# arduino_clone.net
KiCad netlist of a schematic drawn in EAGLE
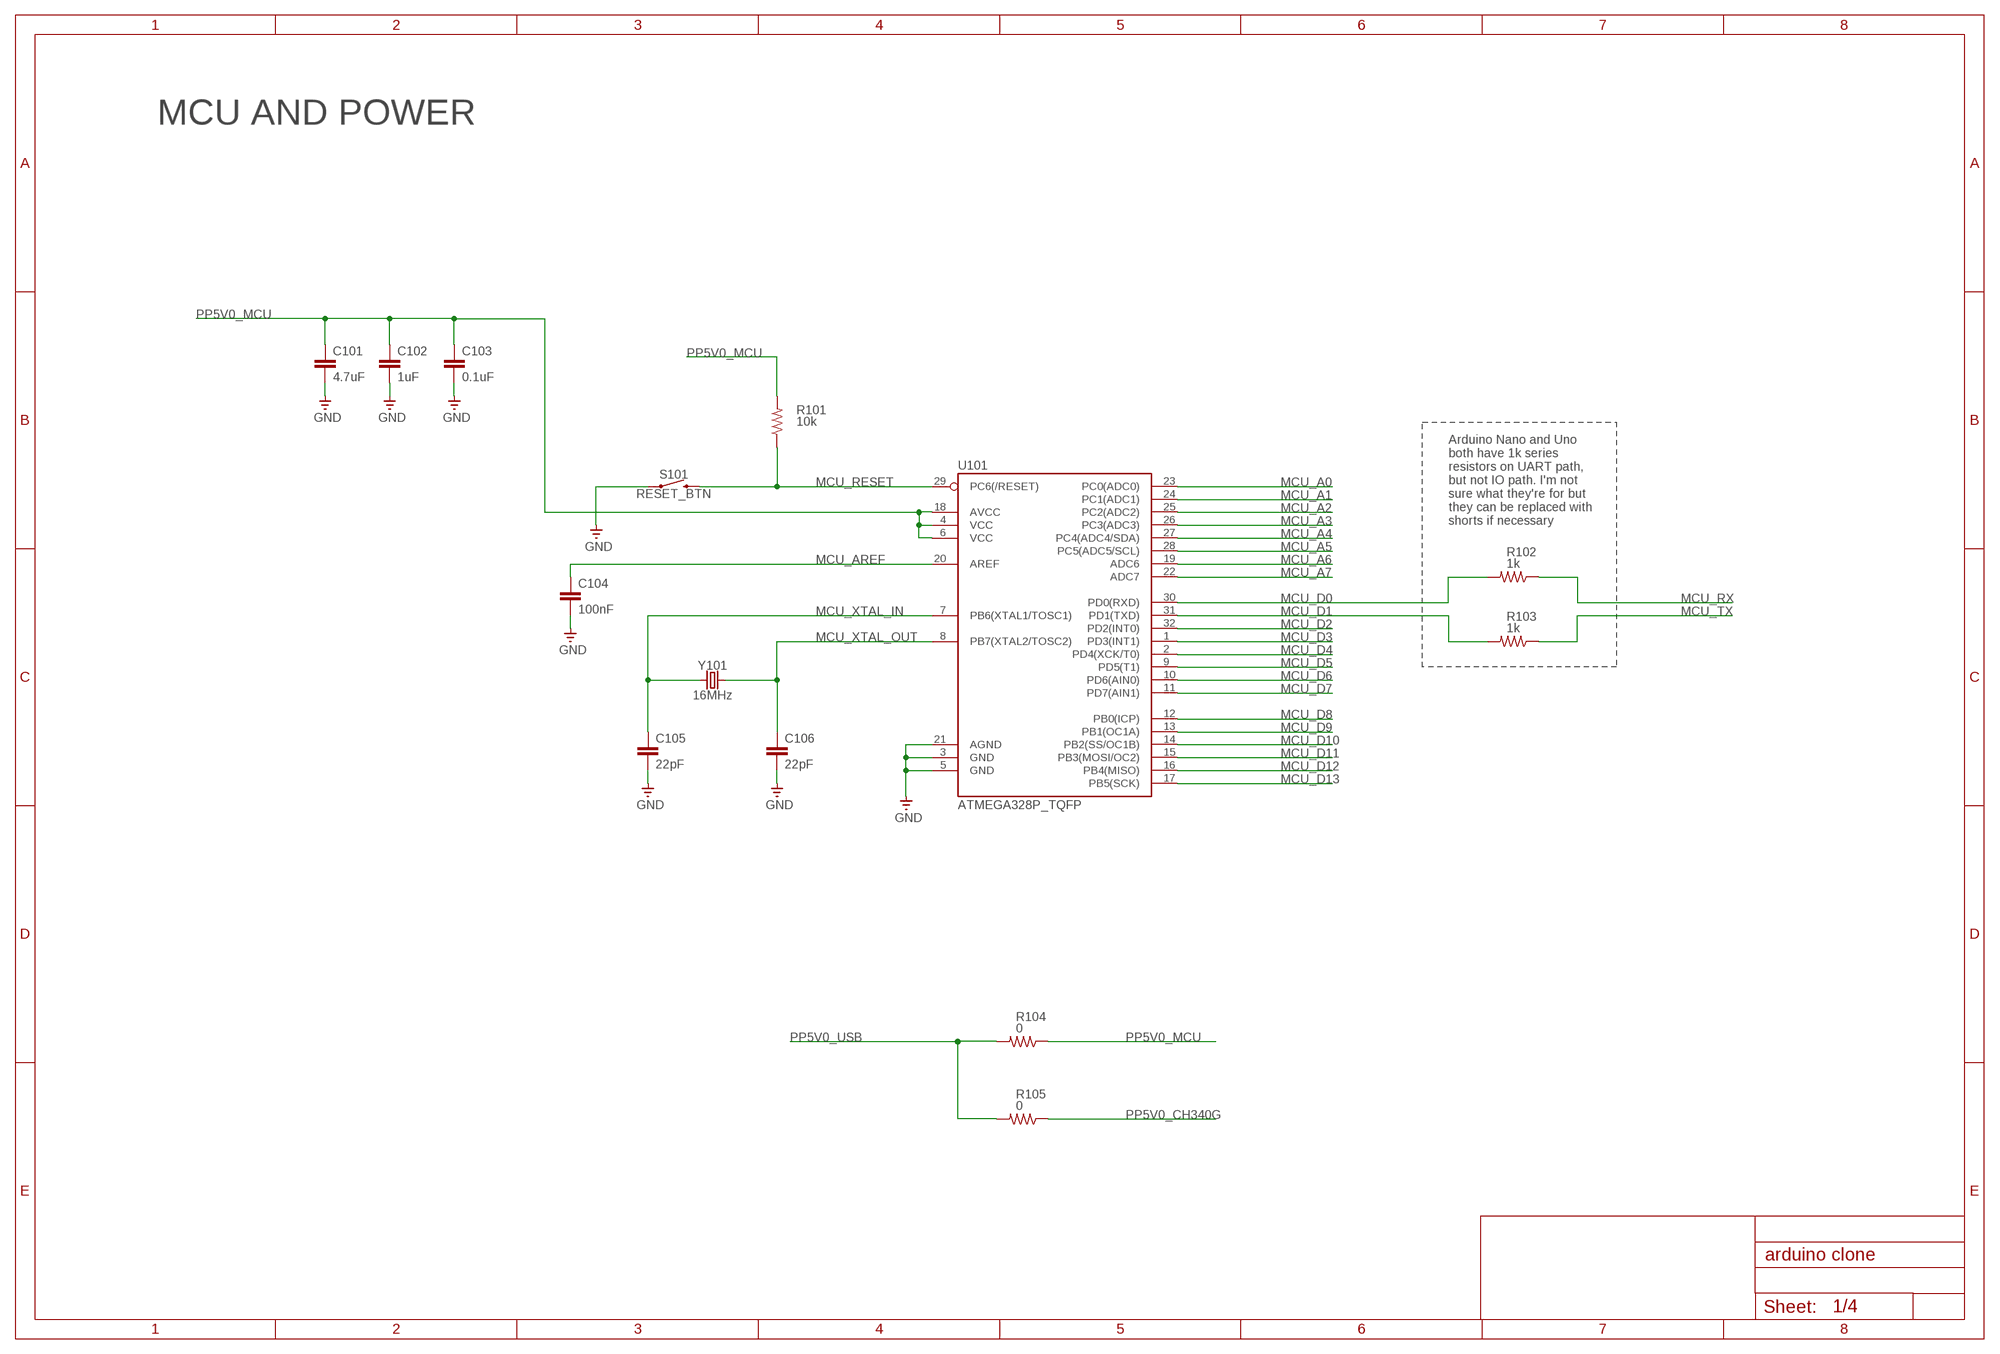
[diagram p0: schematic, sheet 1]
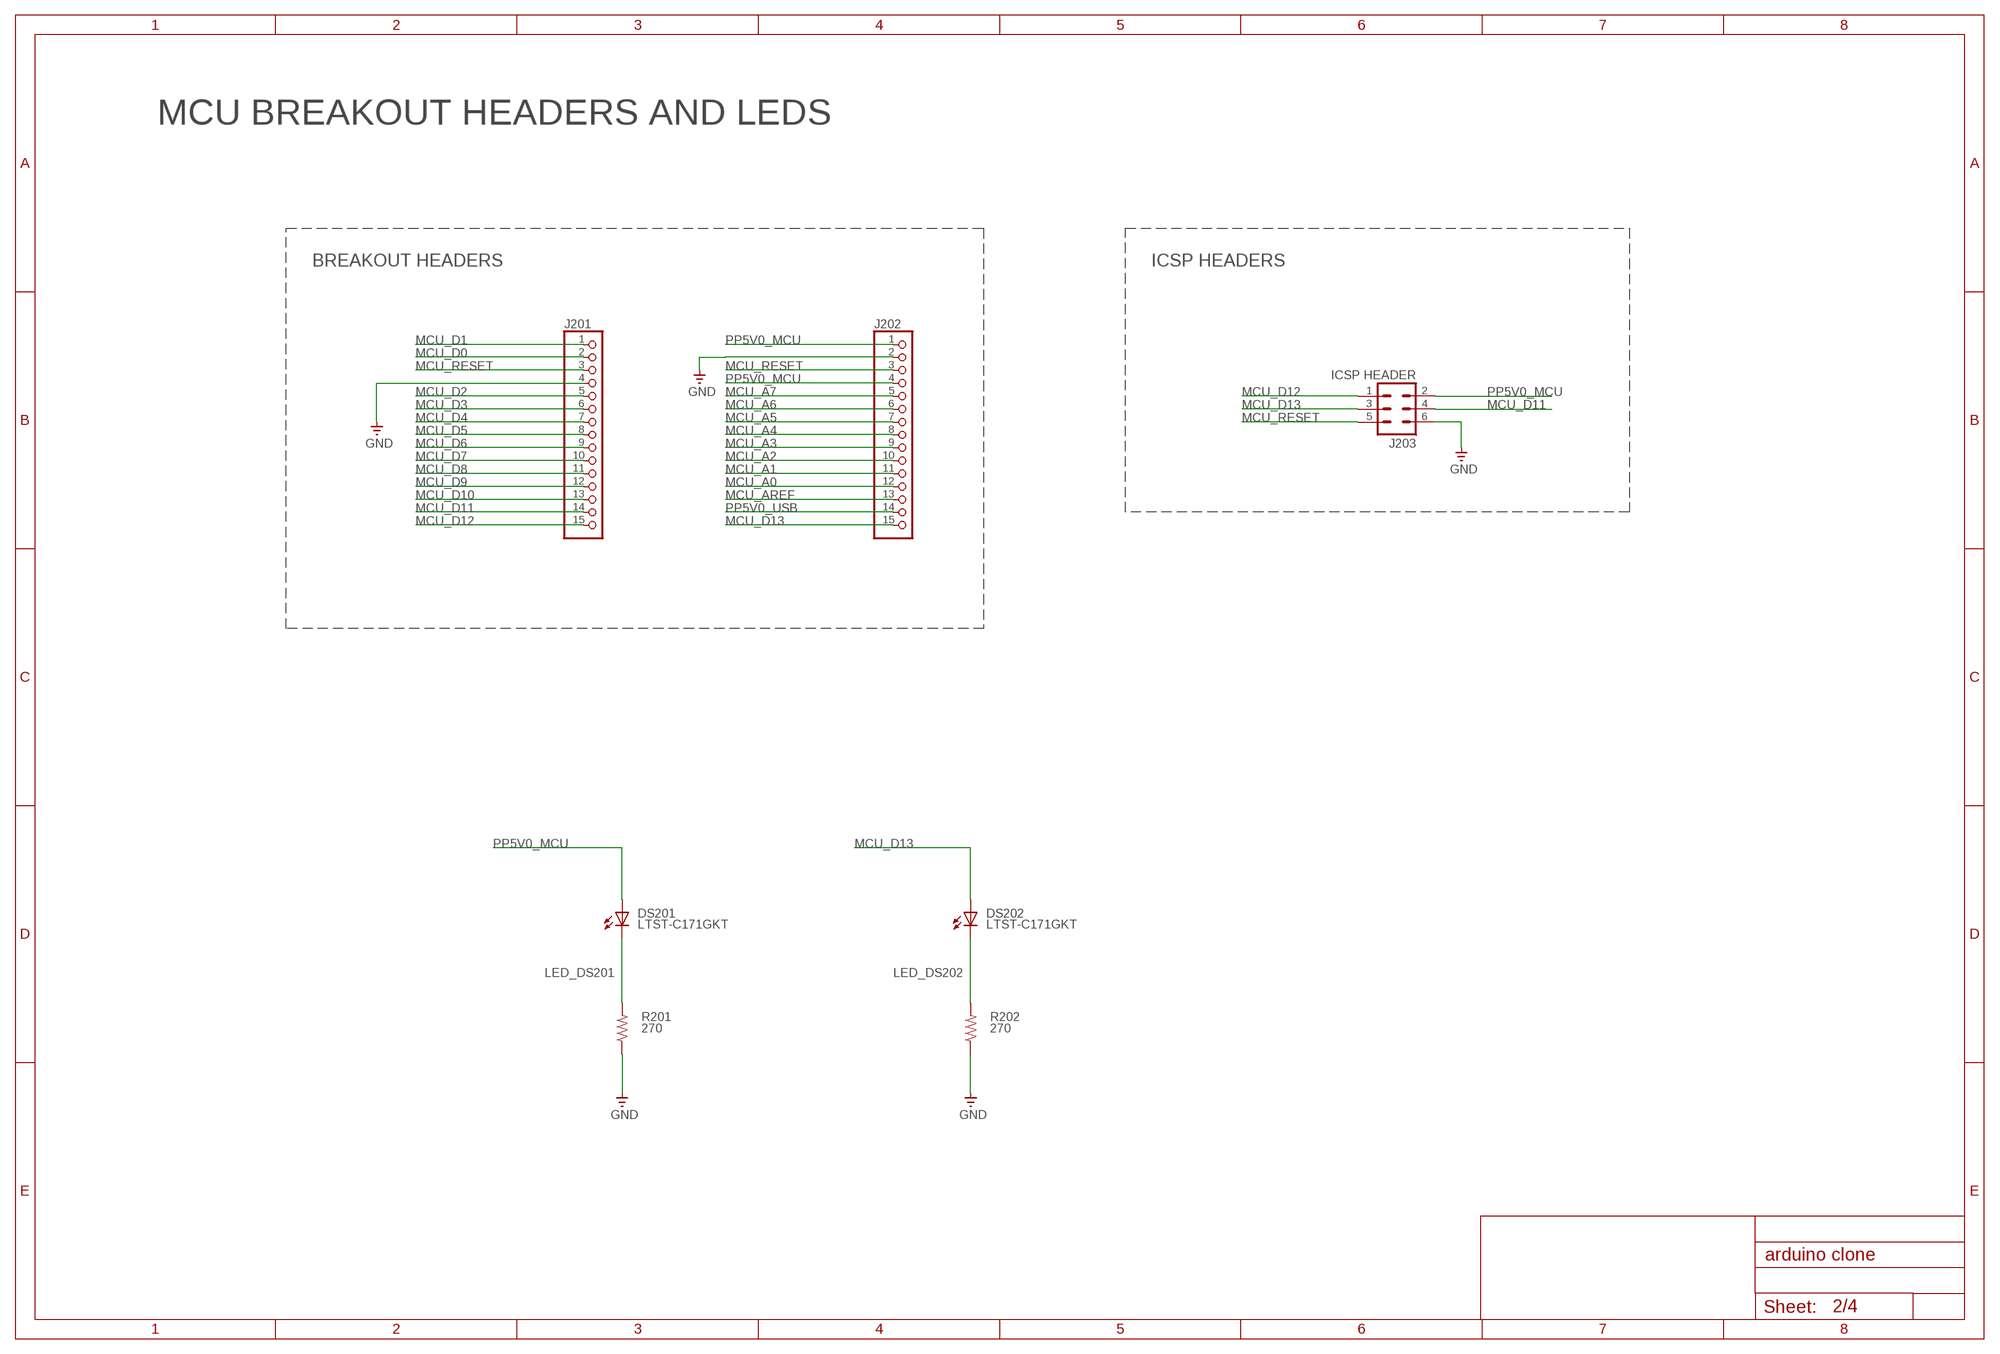
[diagram p1: schematic, sheet 2]
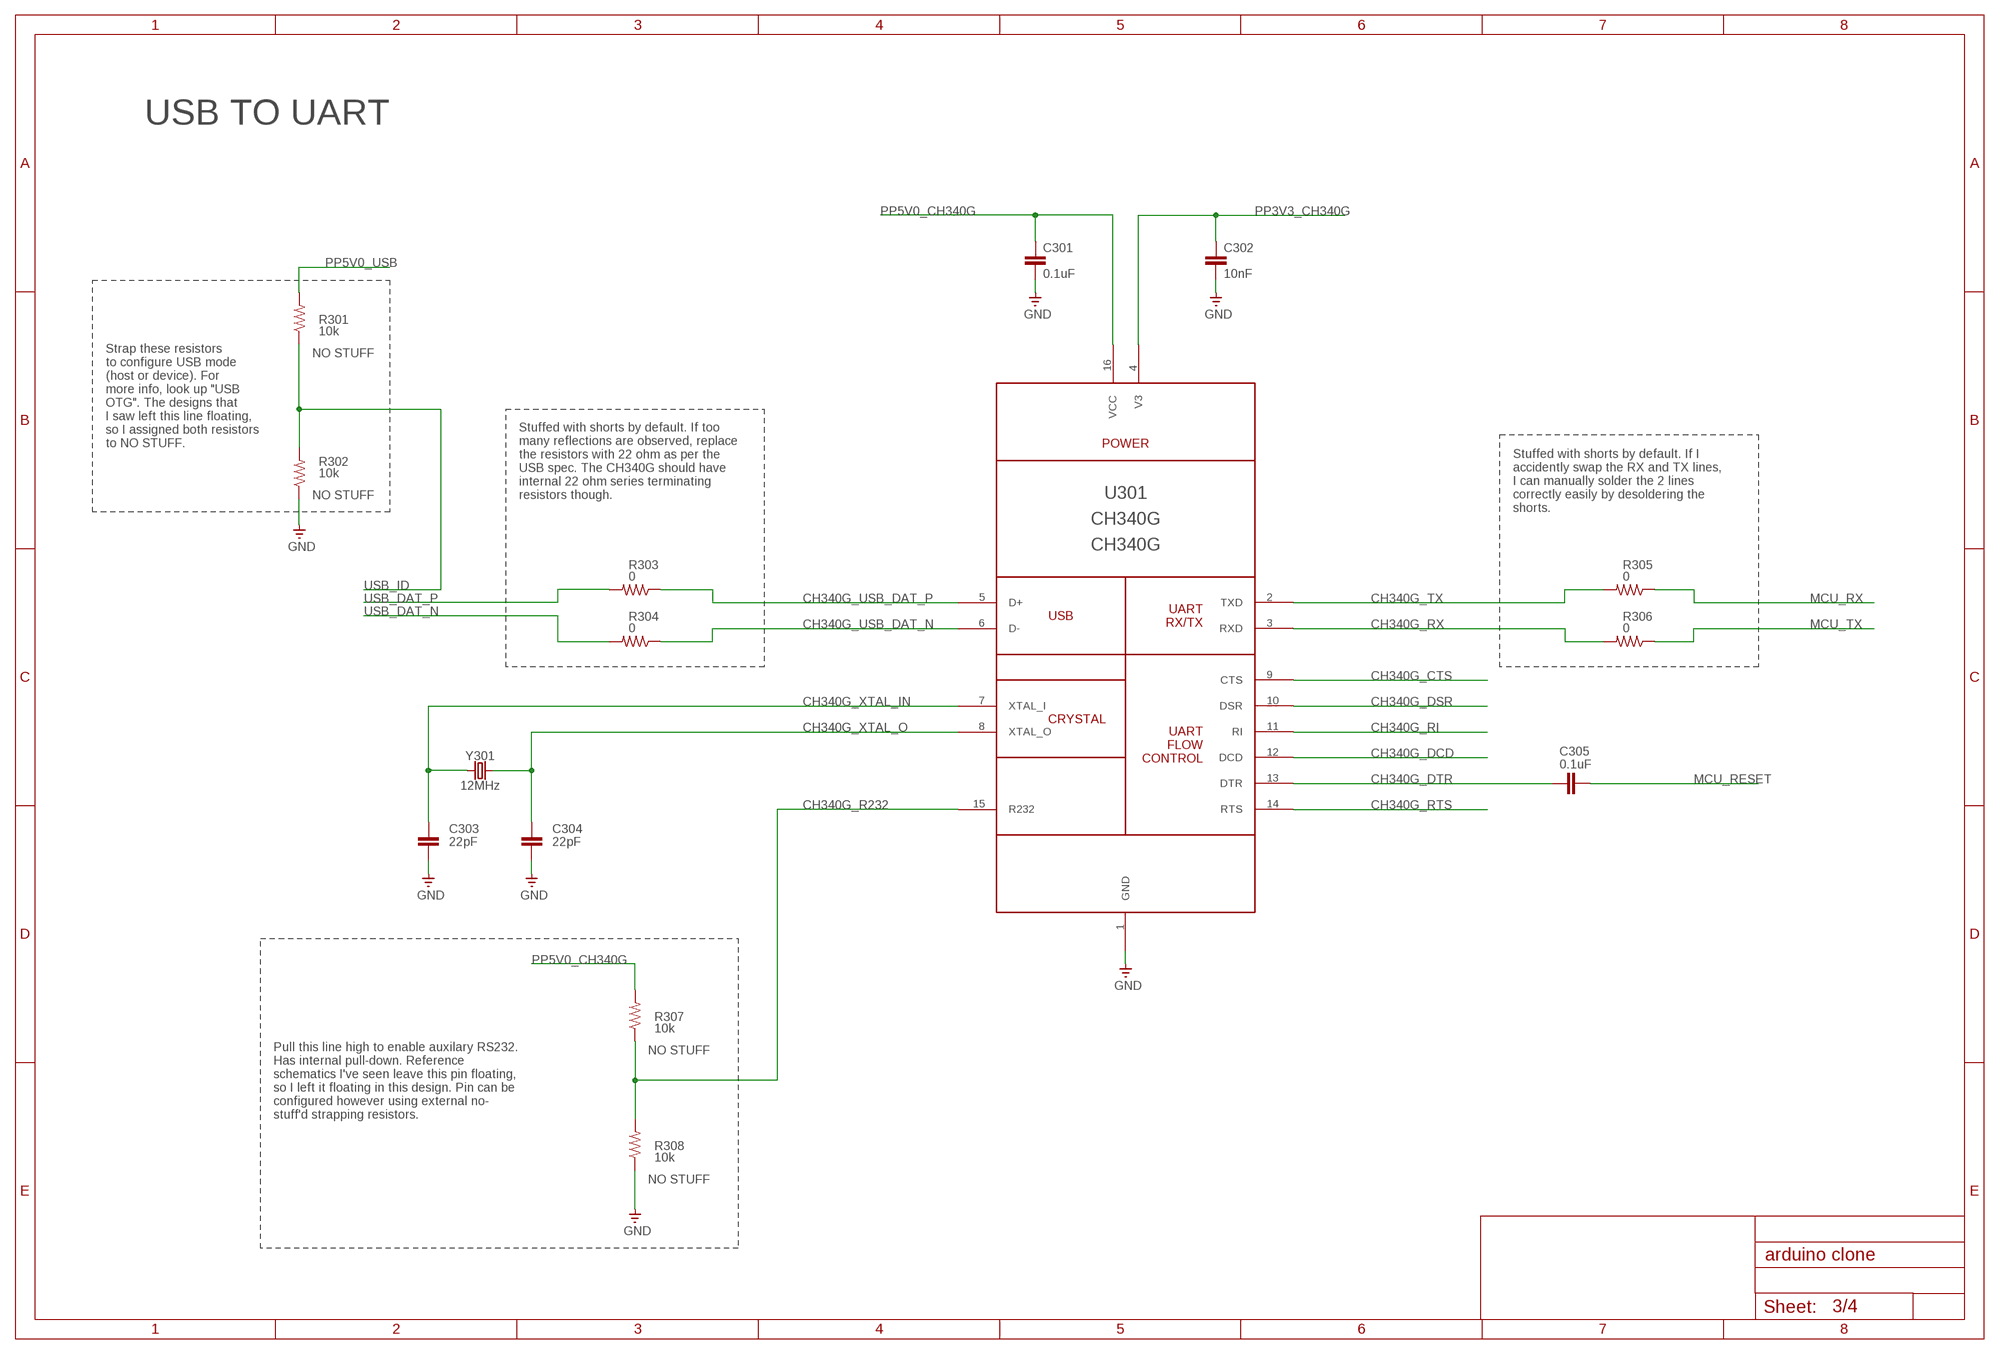
[diagram p2: schematic, sheet 3]
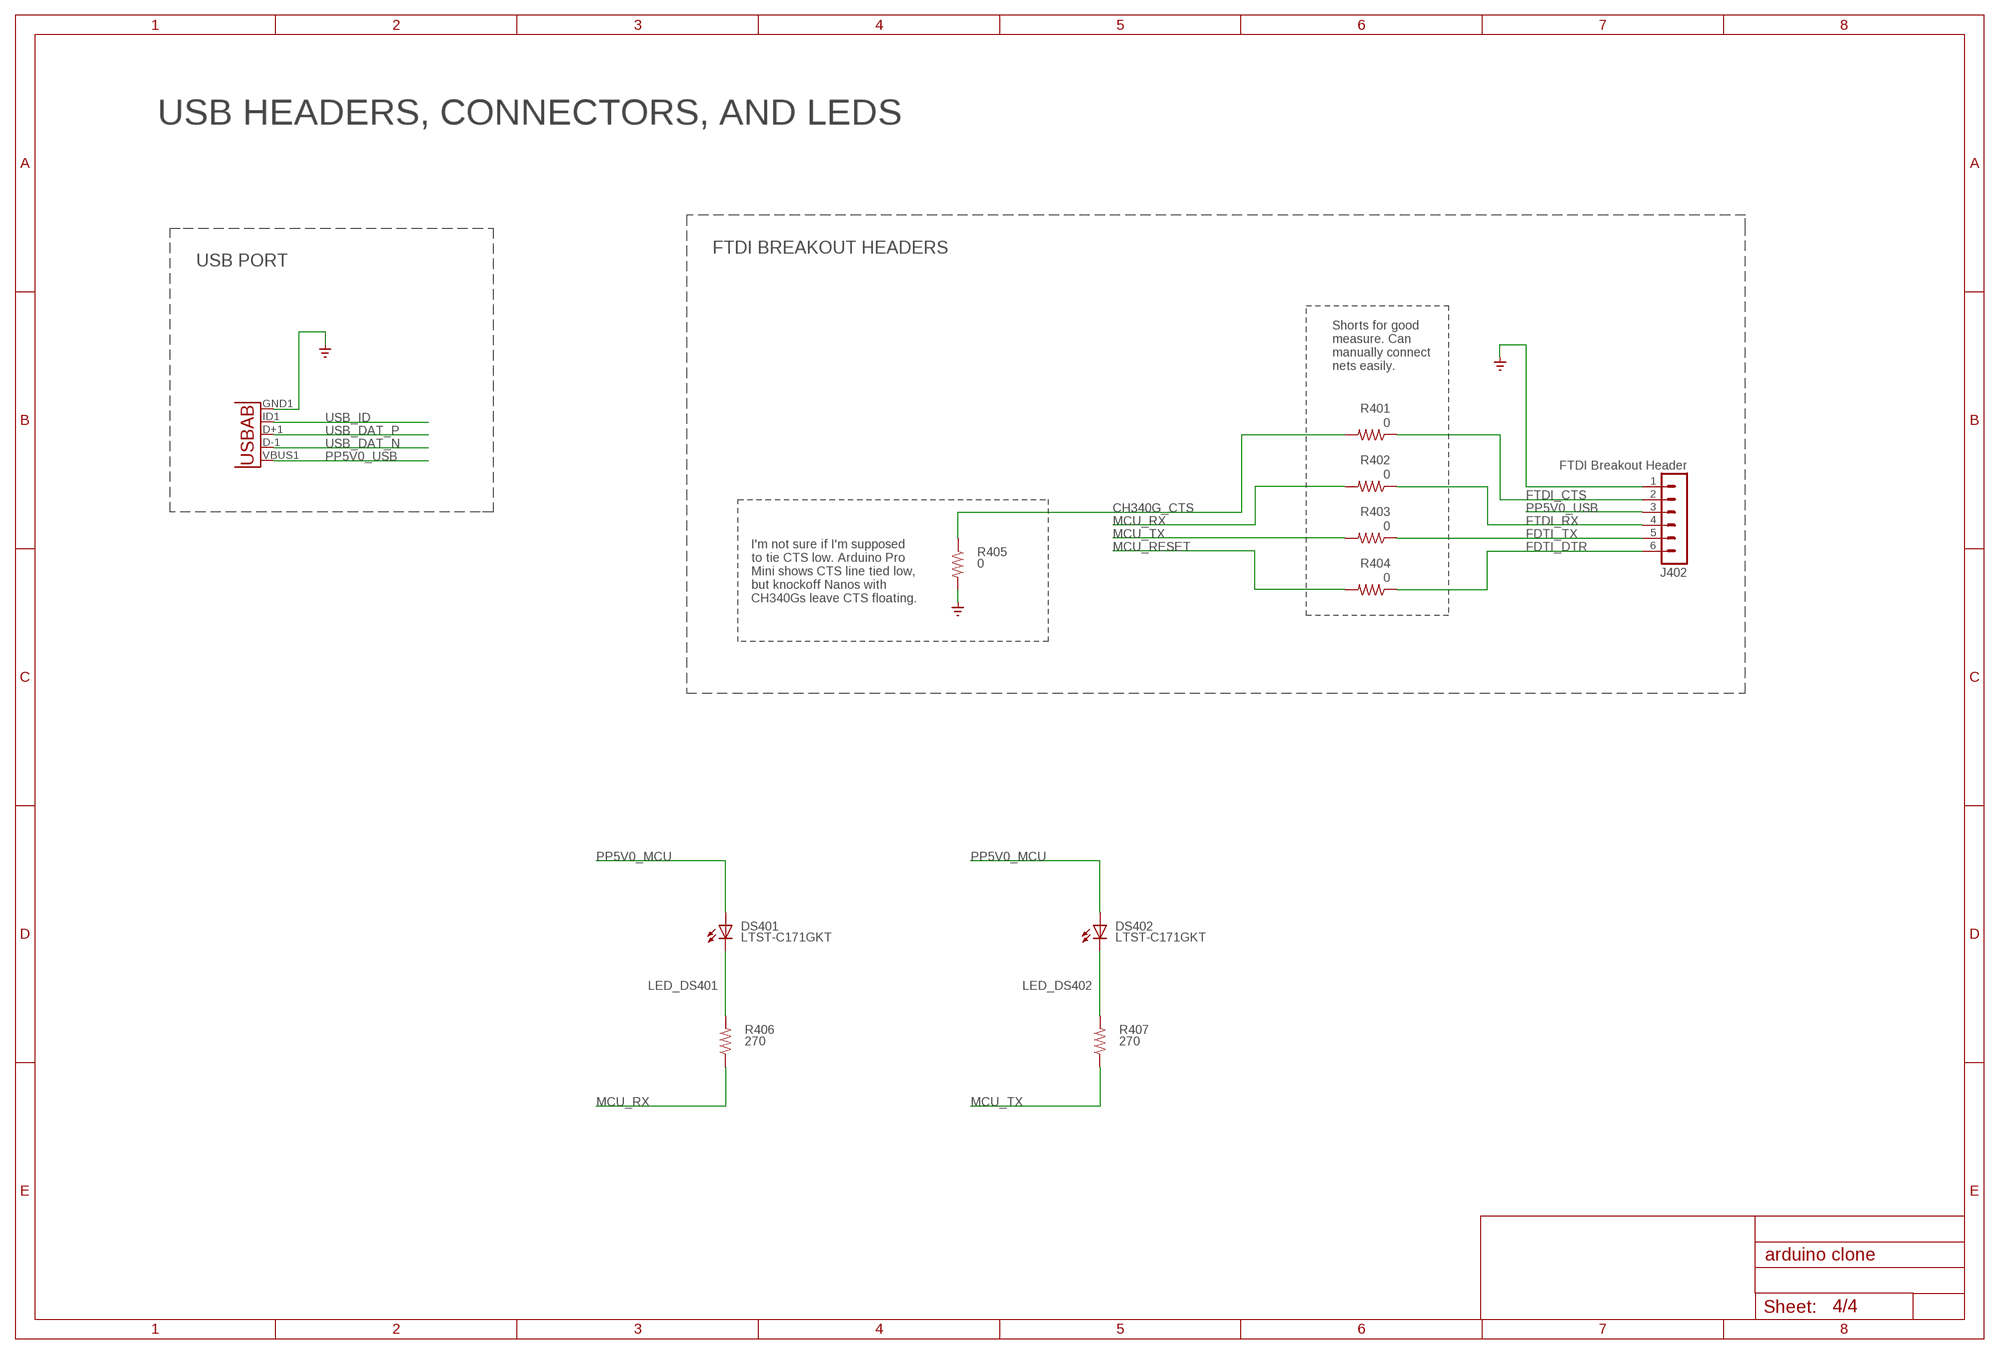
[diagram p3: schematic, sheet 4]

(export (version "E")
  (design (tool "Eeschema 10.0.6"))
  (components
    (comp (ref "C101")
      (value "4.7uF")
      (footprint "eagle-import:C0805")
      (libsource (lib "eagle-import") (part "C-EUC0805"))
    )
    (comp (ref "C102")
      (value "1uF")
      (footprint "eagle-import:C0805")
      (libsource (lib "eagle-import") (part "C-EUC0805"))
    )
    (comp (ref "C103")
      (value "0.1uF")
      (footprint "eagle-import:C0805")
      (libsource (lib "eagle-import") (part "C-EUC0805"))
    )
    (comp (ref "C104")
      (value "100nF")
      (footprint "eagle-import:C0805")
      (libsource (lib "eagle-import") (part "C-EUC0805"))
    )
    (comp (ref "C105")
      (value "22pF")
      (footprint "eagle-import:C0805")
      (libsource (lib "eagle-import") (part "C-EUC0805"))
    )
    (comp (ref "C106")
      (value "22pF")
      (footprint "eagle-import:C0805")
      (libsource (lib "eagle-import") (part "C-EUC0805"))
    )
    (comp (ref "R101")
      (value "10k")
      (footprint "eagle-import:R0805")
      (libsource (lib "eagle-import") (part "R-US_R0805"))
    )
    (comp (ref "R102")
      (value "1k")
      (footprint "eagle-import:R0805")
      (libsource (lib "eagle-import") (part "R-US_R0805"))
    )
    (comp (ref "R103")
      (value "1k")
      (footprint "eagle-import:R0805")
      (libsource (lib "eagle-import") (part "R-US_R0805"))
    )
    (comp (ref "R104")
      (value "0")
      (footprint "eagle-import:R0805")
      (libsource (lib "eagle-import") (part "R-US_R0805"))
    )
    (comp (ref "R105")
      (value "0")
      (footprint "eagle-import:R0805")
      (libsource (lib "eagle-import") (part "R-US_R0805"))
    )
    (comp (ref "S101")
      (value "RESET_BTN")
      (footprint "eagle-import:TACTILE_SWITCH_SMD_6.2MM_TALL")
      (libsource (lib "eagle-import") (part "MOMENTARY-SWITCH-SPST-SMD-6.2MM-TALL"))
    )
    (comp (ref "U101")
      (value "ATMEGA328P_TQFP")
      (footprint "eagle-import:TQFP32-08")
      (libsource (lib "eagle-import") (part "ATMEGA328P_TQFP"))
    )
    (comp (ref "Y101")
      (value "16MHz")
      (footprint "eagle-import:CRYSTAL-SMD-5X3.2-4PAD")
      (libsource (lib "eagle-import") (part "CRYSTAL-16MHZSMD-5X3.2"))
    )
    (comp (ref "C301")
      (value "0.1uF")
      (footprint "eagle-import:C0805")
      (libsource (lib "eagle-import") (part "C-EUC0805"))
    )
    (comp (ref "C302")
      (value "10nF")
      (footprint "eagle-import:C0805")
      (libsource (lib "eagle-import") (part "C-EUC0805"))
    )
    (comp (ref "C303")
      (value "22pF")
      (footprint "eagle-import:C0805")
      (libsource (lib "eagle-import") (part "C-EUC0805"))
    )
    (comp (ref "C304")
      (value "22pF")
      (footprint "eagle-import:C0805")
      (libsource (lib "eagle-import") (part "C-EUC0805"))
    )
    (comp (ref "C305")
      (value "0.1uF")
      (footprint "eagle-import:C0805")
      (libsource (lib "eagle-import") (part "C-EUC0805"))
    )
    (comp (ref "R301")
      (value "10k")
      (footprint "eagle-import:R0805")
      (fields (field (name "STUFF") "NO STUFF"))
      (libsource (lib "eagle-import") (part "R-US_R0805"))
    )
    (comp (ref "R302")
      (value "10k")
      (footprint "eagle-import:R0805")
      (fields (field (name "STUFF") "NO STUFF"))
      (libsource (lib "eagle-import") (part "R-US_R0805"))
    )
    (comp (ref "R303")
      (value "0")
      (footprint "eagle-import:R0805")
      (libsource (lib "eagle-import") (part "R-US_R0805"))
    )
    (comp (ref "R304")
      (value "0")
      (footprint "eagle-import:R0805")
      (libsource (lib "eagle-import") (part "R-US_R0805"))
    )
    (comp (ref "R305")
      (value "0")
      (footprint "eagle-import:R0805")
      (libsource (lib "eagle-import") (part "R-US_R0805"))
    )
    (comp (ref "R306")
      (value "0")
      (footprint "eagle-import:R0805")
      (libsource (lib "eagle-import") (part "R-US_R0805"))
    )
    (comp (ref "R307")
      (value "10k")
      (footprint "eagle-import:R0805")
      (fields (field (name "STUFF") "NO STUFF"))
      (libsource (lib "eagle-import") (part "R-US_R0805"))
    )
    (comp (ref "R308")
      (value "10k")
      (footprint "eagle-import:R0805")
      (fields (field (name "STUFF") "NO STUFF"))
      (libsource (lib "eagle-import") (part "R-US_R0805"))
    )
    (comp (ref "U301")
      (value "CH340G")
      (footprint "eagle-import:SOIC16")
      (libsource (lib "eagle-import") (part "CH340G"))
    )
    (comp (ref "Y301")
      (value "12MHz")
      (footprint "eagle-import:CRYSTAL-SMD-5X3.2-4PAD")
      (libsource (lib "eagle-import") (part "CRYSTAL-12MHZ{dblquote}"))
    )
    (comp (ref "DS201")
      (value "LTST-C171GKT")
      (footprint "eagle-import:CHIPLED_0805")
      (libsource (lib "eagle-import") (part "LEDCHIPLED_0805"))
    )
    (comp (ref "DS202")
      (value "LTST-C171GKT")
      (footprint "eagle-import:CHIPLED_0805")
      (libsource (lib "eagle-import") (part "LEDCHIPLED_0805"))
    )
    (comp (ref "J201")
      (value "PINHD-1X15-CB")
      (footprint "eagle-import:1X15-CB")
      (libsource (lib "eagle-import") (part "PINHD-1X15-CB"))
    )
    (comp (ref "J202")
      (value "PINHD-1X15-CB")
      (footprint "eagle-import:1X15-CB")
      (libsource (lib "eagle-import") (part "PINHD-1X15-CB"))
    )
    (comp (ref "J203")
      (value "ICSP HEADER")
      (footprint "eagle-import:MA03-2")
      (libsource (lib "eagle-import") (part "MA03-2"))
    )
    (comp (ref "R201")
      (value "270")
      (footprint "eagle-import:M0805")
      (libsource (lib "eagle-import") (part "R-US_M0805"))
    )
    (comp (ref "R202")
      (value "270")
      (footprint "eagle-import:M0805")
      (libsource (lib "eagle-import") (part "R-US_M0805"))
    )
    (comp (ref "DS401")
      (value "LTST-C171GKT")
      (footprint "eagle-import:CHIPLED_0805")
      (libsource (lib "eagle-import") (part "LEDCHIPLED_0805"))
    )
    (comp (ref "DS402")
      (value "LTST-C171GKT")
      (footprint "eagle-import:CHIPLED_0805")
      (libsource (lib "eagle-import") (part "LEDCHIPLED_0805"))
    )
    (comp (ref "J401")
      (value "USB-ABIN&OUT")
      (footprint "eagle-import:USB-AB-MICRO-SMD-V03-IN&OUT")
      (libsource (lib "eagle-import") (part "USB-ABIN&OUT"))
    )
    (comp (ref "J402")
      (value "FTDI Breakout Header")
      (footprint "eagle-import:MA06-1")
      (libsource (lib "eagle-import") (part "MA06-1"))
    )
    (comp (ref "R401")
      (value "0")
      (footprint "eagle-import:R0805")
      (libsource (lib "eagle-import") (part "R-US_R0805"))
    )
    (comp (ref "R402")
      (value "0")
      (footprint "eagle-import:R0805")
      (libsource (lib "eagle-import") (part "R-US_R0805"))
    )
    (comp (ref "R403")
      (value "0")
      (footprint "eagle-import:R0805")
      (libsource (lib "eagle-import") (part "R-US_R0805"))
    )
    (comp (ref "R404")
      (value "0")
      (footprint "eagle-import:R0805")
      (libsource (lib "eagle-import") (part "R-US_R0805"))
    )
    (comp (ref "R405")
      (value "0")
      (footprint "eagle-import:R0805")
      (libsource (lib "eagle-import") (part "R-US_R0805"))
    )
    (comp (ref "R406")
      (value "270")
      (footprint "eagle-import:M0805")
      (libsource (lib "eagle-import") (part "R-US_M0805"))
    )
    (comp (ref "R407")
      (value "270")
      (footprint "eagle-import:M0805")
      (libsource (lib "eagle-import") (part "R-US_M0805"))
    )
  )
  (nets
    (net (code "1") (name "CH340G_CTS") (class "Default")
      (node (ref "R401") (pin "2") (pinfunction "2_2") (pintype "passive"))
      (node (ref "R405") (pin "1") (pinfunction "1_1") (pintype "passive"))
      (node (ref "U301") (pin "9") (pinfunction "CTS_9") (pintype "input"))
    )
    (net (code "2") (name "CH340G_DCD") (class "Default")
      (node (ref "U301") (pin "12") (pinfunction "DCD_12") (pintype "input"))
    )
    (net (code "3") (name "CH340G_DSR") (class "Default")
      (node (ref "U301") (pin "10") (pinfunction "DSR_10") (pintype "input"))
    )
    (net (code "4") (name "CH340G_DTR") (class "Default")
      (node (ref "C305") (pin "1") (pinfunction "1_1") (pintype "passive"))
      (node (ref "U301") (pin "13") (pinfunction "DTR_13") (pintype "output"))
    )
    (net (code "5") (name "CH340G_R232") (class "Default")
      (node (ref "R307") (pin "1") (pinfunction "1_1") (pintype "passive"))
      (node (ref "R308") (pin "2") (pinfunction "2_2") (pintype "passive"))
      (node (ref "U301") (pin "15") (pinfunction "R232_15") (pintype "input"))
    )
    (net (code "6") (name "CH340G_RI") (class "Default")
      (node (ref "U301") (pin "11") (pinfunction "RI_11") (pintype "input"))
    )
    (net (code "7") (name "CH340G_RTS") (class "Default")
      (node (ref "U301") (pin "14") (pinfunction "RTS_14") (pintype "output"))
    )
    (net (code "8") (name "CH340G_RX") (class "Default")
      (node (ref "R306") (pin "2") (pinfunction "2_2") (pintype "passive"))
      (node (ref "U301") (pin "3") (pinfunction "RXD_3") (pintype "output"))
    )
    (net (code "9") (name "CH340G_TX") (class "Default")
      (node (ref "R305") (pin "2") (pinfunction "2_2") (pintype "passive"))
      (node (ref "U301") (pin "2") (pinfunction "TXD_2") (pintype "output"))
    )
    (net (code "10") (name "CH340G_USB_DAT_N") (class "Default")
      (node (ref "R304") (pin "1") (pinfunction "1_1") (pintype "passive"))
      (node (ref "U301") (pin "6") (pinfunction "D-_6") (pintype "bidirectional"))
    )
    (net (code "11") (name "CH340G_USB_DAT_P") (class "Default")
      (node (ref "R303") (pin "1") (pinfunction "1_1") (pintype "passive"))
      (node (ref "U301") (pin "5") (pinfunction "D+_5") (pintype "bidirectional"))
    )
    (net (code "12") (name "CH340G_XTAL_IN") (class "Default")
      (node (ref "C303") (pin "1") (pinfunction "1_1") (pintype "passive"))
      (node (ref "U301") (pin "7") (pinfunction "XTAL_I_7") (pintype "bidirectional"))
      (node (ref "Y301") (pin "1") (pinfunction "1_1") (pintype "passive"))
    )
    (net (code "13") (name "CH340G_XTAL_O") (class "Default")
      (node (ref "C304") (pin "1") (pinfunction "1_1") (pintype "passive"))
      (node (ref "U301") (pin "8") (pinfunction "XTAL_O_8") (pintype "bidirectional"))
      (node (ref "Y301") (pin "3") (pinfunction "2_3") (pintype "passive"))
    )
    (net (code "14") (name "FDTI_DTR") (class "Default")
      (node (ref "J402") (pin "6") (pinfunction "6_6") (pintype "passive"))
      (node (ref "R404") (pin "1") (pinfunction "1_1") (pintype "passive"))
    )
    (net (code "15") (name "FDTI_TX") (class "Default")
      (node (ref "J402") (pin "5") (pinfunction "5_5") (pintype "passive"))
      (node (ref "R403") (pin "1") (pinfunction "1_1") (pintype "passive"))
    )
    (net (code "16") (name "FTDI_CTS") (class "Default")
      (node (ref "J402") (pin "2") (pinfunction "2_2") (pintype "passive"))
      (node (ref "R401") (pin "1") (pinfunction "1_1") (pintype "passive"))
    )
    (net (code "17") (name "FTDI_RX") (class "Default")
      (node (ref "J402") (pin "4") (pinfunction "4_4") (pintype "passive"))
      (node (ref "R402") (pin "1") (pinfunction "1_1") (pintype "passive"))
    )
    (net (code "18") (name "GND") (class "Default")
      (node (ref "C101") (pin "2") (pinfunction "2_2") (pintype "passive"))
      (node (ref "C102") (pin "2") (pinfunction "2_2") (pintype "passive"))
      (node (ref "C103") (pin "2") (pinfunction "2_2") (pintype "passive"))
      (node (ref "C104") (pin "2") (pinfunction "2_2") (pintype "passive"))
      (node (ref "C105") (pin "2") (pinfunction "2_2") (pintype "passive"))
      (node (ref "C106") (pin "2") (pinfunction "2_2") (pintype "passive"))
      (node (ref "C301") (pin "2") (pinfunction "2_2") (pintype "passive"))
      (node (ref "C302") (pin "2") (pinfunction "2_2") (pintype "passive"))
      (node (ref "C303") (pin "2") (pinfunction "2_2") (pintype "passive"))
      (node (ref "C304") (pin "2") (pinfunction "2_2") (pintype "passive"))
      (node (ref "J201") (pin "4") (pinfunction "4_4") (pintype "passive"))
      (node (ref "J202") (pin "2") (pinfunction "2_2") (pintype "passive"))
      (node (ref "J203") (pin "6") (pinfunction "6_6") (pintype "passive"))
      (node (ref "J401") (pin "GND1") (pinfunction "GND_GND1") (pintype "bidirectional"))
      (node (ref "J402") (pin "1") (pinfunction "1_1") (pintype "passive"))
      (node (ref "R201") (pin "1") (pinfunction "1_1") (pintype "passive"))
      (node (ref "R202") (pin "1") (pinfunction "1_1") (pintype "passive"))
      (node (ref "R302") (pin "1") (pinfunction "1_1") (pintype "passive"))
      (node (ref "R308") (pin "1") (pinfunction "1_1") (pintype "passive"))
      (node (ref "R405") (pin "2") (pinfunction "2_2") (pintype "passive"))
      (node (ref "S101") (pin "A2") (pinfunction "1_A2") (pintype "passive"))
      (node (ref "U101") (pin "21") (pinfunction "AGND_21") (pintype "bidirectional"))
      (node (ref "U101") (pin "3") (pinfunction "GND_3") (pintype "bidirectional"))
      (node (ref "U101") (pin "5") (pinfunction "GND_5") (pintype "bidirectional"))
      (node (ref "U301") (pin "1") (pinfunction "GND_1") (pintype "power_in"))
    )
    (net (code "19") (name "LED_DS201") (class "Default")
      (node (ref "DS201") (pin "C") (pinfunction "C_C") (pintype "passive"))
      (node (ref "R201") (pin "2") (pinfunction "2_2") (pintype "passive"))
    )
    (net (code "20") (name "LED_DS202") (class "Default")
      (node (ref "DS202") (pin "C") (pinfunction "C_C") (pintype "passive"))
      (node (ref "R202") (pin "2") (pinfunction "2_2") (pintype "passive"))
    )
    (net (code "21") (name "LED_DS401") (class "Default")
      (node (ref "DS401") (pin "C") (pinfunction "C_C") (pintype "passive"))
      (node (ref "R406") (pin "2") (pinfunction "2_2") (pintype "passive"))
    )
    (net (code "22") (name "LED_DS402") (class "Default")
      (node (ref "DS402") (pin "C") (pinfunction "C_C") (pintype "passive"))
      (node (ref "R407") (pin "2") (pinfunction "2_2") (pintype "passive"))
    )
    (net (code "23") (name "MCU_A0") (class "Default")
      (node (ref "J202") (pin "12") (pinfunction "12_12") (pintype "passive"))
      (node (ref "U101") (pin "23") (pinfunction "PC0(ADC0)_23") (pintype "bidirectional"))
    )
    (net (code "24") (name "MCU_A1") (class "Default")
      (node (ref "J202") (pin "11") (pinfunction "11_11") (pintype "passive"))
      (node (ref "U101") (pin "24") (pinfunction "PC1(ADC1)_24") (pintype "bidirectional"))
    )
    (net (code "25") (name "MCU_A2") (class "Default")
      (node (ref "J202") (pin "10") (pinfunction "10_10") (pintype "passive"))
      (node (ref "U101") (pin "25") (pinfunction "PC2(ADC2)_25") (pintype "bidirectional"))
    )
    (net (code "26") (name "MCU_A3") (class "Default")
      (node (ref "J202") (pin "9") (pinfunction "9_9") (pintype "passive"))
      (node (ref "U101") (pin "26") (pinfunction "PC3(ADC3)_26") (pintype "bidirectional"))
    )
    (net (code "27") (name "MCU_A4") (class "Default")
      (node (ref "J202") (pin "8") (pinfunction "8_8") (pintype "passive"))
      (node (ref "U101") (pin "27") (pinfunction "PC4(ADC4/SDA)_27") (pintype "bidirectional"))
    )
    (net (code "28") (name "MCU_A5") (class "Default")
      (node (ref "J202") (pin "7") (pinfunction "7_7") (pintype "passive"))
      (node (ref "U101") (pin "28") (pinfunction "PC5(ADC5/SCL)_28") (pintype "bidirectional"))
    )
    (net (code "29") (name "MCU_A6") (class "Default")
      (node (ref "J202") (pin "6") (pinfunction "6_6") (pintype "passive"))
      (node (ref "U101") (pin "19") (pinfunction "ADC6_19") (pintype "bidirectional"))
    )
    (net (code "30") (name "MCU_A7") (class "Default")
      (node (ref "J202") (pin "5") (pinfunction "5_5") (pintype "passive"))
      (node (ref "U101") (pin "22") (pinfunction "ADC7_22") (pintype "bidirectional"))
    )
    (net (code "31") (name "MCU_AREF") (class "Default")
      (node (ref "C104") (pin "1") (pinfunction "1_1") (pintype "passive"))
      (node (ref "J202") (pin "13") (pinfunction "13_13") (pintype "passive"))
      (node (ref "U101") (pin "20") (pinfunction "AREF_20") (pintype "bidirectional"))
    )
    (net (code "32") (name "MCU_D0") (class "Default")
      (node (ref "J201") (pin "2") (pinfunction "2_2") (pintype "passive"))
      (node (ref "R102") (pin "2") (pinfunction "2_2") (pintype "passive"))
      (node (ref "U101") (pin "30") (pinfunction "PD0(RXD)_30") (pintype "bidirectional"))
    )
    (net (code "33") (name "MCU_D1") (class "Default")
      (node (ref "J201") (pin "1") (pinfunction "1_1") (pintype "passive"))
      (node (ref "R103") (pin "2") (pinfunction "2_2") (pintype "passive"))
      (node (ref "U101") (pin "31") (pinfunction "PD1(TXD)_31") (pintype "bidirectional"))
    )
    (net (code "34") (name "MCU_D2") (class "Default")
      (node (ref "J201") (pin "5") (pinfunction "5_5") (pintype "passive"))
      (node (ref "U101") (pin "32") (pinfunction "PD2(INT0)_32") (pintype "bidirectional"))
    )
    (net (code "35") (name "MCU_D3") (class "Default")
      (node (ref "J201") (pin "6") (pinfunction "6_6") (pintype "passive"))
      (node (ref "U101") (pin "1") (pinfunction "PD3(INT1)_1") (pintype "bidirectional"))
    )
    (net (code "36") (name "MCU_D4") (class "Default")
      (node (ref "J201") (pin "7") (pinfunction "7_7") (pintype "passive"))
      (node (ref "U101") (pin "2") (pinfunction "PD4(XCK/T0)_2") (pintype "bidirectional"))
    )
    (net (code "37") (name "MCU_D5") (class "Default")
      (node (ref "J201") (pin "8") (pinfunction "8_8") (pintype "passive"))
      (node (ref "U101") (pin "9") (pinfunction "PD5(T1)_9") (pintype "bidirectional"))
    )
    (net (code "38") (name "MCU_D6") (class "Default")
      (node (ref "J201") (pin "9") (pinfunction "9_9") (pintype "passive"))
      (node (ref "U101") (pin "10") (pinfunction "PD6(AIN0)_10") (pintype "bidirectional"))
    )
    (net (code "39") (name "MCU_D7") (class "Default")
      (node (ref "J201") (pin "10") (pinfunction "10_10") (pintype "passive"))
      (node (ref "U101") (pin "11") (pinfunction "PD7(AIN1)_11") (pintype "bidirectional"))
    )
    (net (code "40") (name "MCU_D8") (class "Default")
      (node (ref "J201") (pin "11") (pinfunction "11_11") (pintype "passive"))
      (node (ref "U101") (pin "12") (pinfunction "PB0(ICP)_12") (pintype "bidirectional"))
    )
    (net (code "41") (name "MCU_D9") (class "Default")
      (node (ref "J201") (pin "12") (pinfunction "12_12") (pintype "passive"))
      (node (ref "U101") (pin "13") (pinfunction "PB1(OC1A)_13") (pintype "bidirectional"))
    )
    (net (code "42") (name "MCU_D10") (class "Default")
      (node (ref "J201") (pin "13") (pinfunction "13_13") (pintype "passive"))
      (node (ref "U101") (pin "14") (pinfunction "PB2(SS/OC1B)_14") (pintype "bidirectional"))
    )
    (net (code "43") (name "MCU_D11") (class "Default")
      (node (ref "J201") (pin "14") (pinfunction "14_14") (pintype "passive"))
      (node (ref "J203") (pin "4") (pinfunction "4_4") (pintype "passive"))
      (node (ref "U101") (pin "15") (pinfunction "PB3(MOSI/OC2)_15") (pintype "bidirectional"))
    )
    (net (code "44") (name "MCU_D12") (class "Default")
      (node (ref "J201") (pin "15") (pinfunction "15_15") (pintype "passive"))
      (node (ref "J203") (pin "1") (pinfunction "1_1") (pintype "passive"))
      (node (ref "U101") (pin "16") (pinfunction "PB4(MISO)_16") (pintype "bidirectional"))
    )
    (net (code "45") (name "MCU_D13") (class "Default")
      (node (ref "DS202") (pin "A") (pinfunction "A_A") (pintype "passive"))
      (node (ref "J202") (pin "15") (pinfunction "15_15") (pintype "passive"))
      (node (ref "J203") (pin "3") (pinfunction "3_3") (pintype "passive"))
      (node (ref "U101") (pin "17") (pinfunction "PB5(SCK)_17") (pintype "bidirectional"))
    )
    (net (code "46") (name "MCU_RESET") (class "Default")
      (node (ref "C305") (pin "2") (pinfunction "2_2") (pintype "passive"))
      (node (ref "J201") (pin "3") (pinfunction "3_3") (pintype "passive"))
      (node (ref "J202") (pin "3") (pinfunction "3_3") (pintype "passive"))
      (node (ref "J203") (pin "5") (pinfunction "5_5") (pintype "passive"))
      (node (ref "R101") (pin "1") (pinfunction "1_1") (pintype "passive"))
      (node (ref "R404") (pin "2") (pinfunction "2_2") (pintype "passive"))
      (node (ref "S101") (pin "B2") (pinfunction "2_B2") (pintype "passive"))
      (node (ref "U101") (pin "29") (pinfunction "PC6(/RESET)_29") (pintype "bidirectional"))
    )
    (net (code "47") (name "MCU_RX") (class "Default")
      (node (ref "R102") (pin "1") (pinfunction "1_1") (pintype "passive"))
      (node (ref "R305") (pin "1") (pinfunction "1_1") (pintype "passive"))
      (node (ref "R402") (pin "2") (pinfunction "2_2") (pintype "passive"))
      (node (ref "R406") (pin "1") (pinfunction "1_1") (pintype "passive"))
    )
    (net (code "48") (name "MCU_TX") (class "Default")
      (node (ref "R103") (pin "1") (pinfunction "1_1") (pintype "passive"))
      (node (ref "R306") (pin "1") (pinfunction "1_1") (pintype "passive"))
      (node (ref "R403") (pin "2") (pinfunction "2_2") (pintype "passive"))
      (node (ref "R407") (pin "1") (pinfunction "1_1") (pintype "passive"))
    )
    (net (code "49") (name "MCU_XTAL_IN") (class "Default")
      (node (ref "C105") (pin "1") (pinfunction "1_1") (pintype "passive"))
      (node (ref "U101") (pin "7") (pinfunction "PB6(XTAL1/TOSC1)_7") (pintype "bidirectional"))
      (node (ref "Y101") (pin "1") (pinfunction "1_1") (pintype "passive"))
    )
    (net (code "50") (name "MCU_XTAL_OUT") (class "Default")
      (node (ref "C106") (pin "1") (pinfunction "1_1") (pintype "passive"))
      (node (ref "U101") (pin "8") (pinfunction "PB7(XTAL2/TOSC2)_8") (pintype "bidirectional"))
      (node (ref "Y101") (pin "3") (pinfunction "2_3") (pintype "passive"))
    )
    (net (code "51") (name "PP3V3_CH340G") (class "Default")
      (node (ref "C302") (pin "1") (pinfunction "1_1") (pintype "passive"))
      (node (ref "U301") (pin "4") (pinfunction "V3_4") (pintype "power_in"))
    )
    (net (code "52") (name "PP5V0_CH340G") (class "Default")
      (node (ref "C301") (pin "1") (pinfunction "1_1") (pintype "passive"))
      (node (ref "R105") (pin "1") (pinfunction "1_1") (pintype "passive"))
      (node (ref "R307") (pin "2") (pinfunction "2_2") (pintype "passive"))
      (node (ref "U301") (pin "16") (pinfunction "VCC_16") (pintype "power_in"))
    )
    (net (code "53") (name "PP5V0_MCU") (class "Default")
      (node (ref "C101") (pin "1") (pinfunction "1_1") (pintype "passive"))
      (node (ref "C102") (pin "1") (pinfunction "1_1") (pintype "passive"))
      (node (ref "C103") (pin "1") (pinfunction "1_1") (pintype "passive"))
      (node (ref "DS201") (pin "A") (pinfunction "A_A") (pintype "passive"))
      (node (ref "DS401") (pin "A") (pinfunction "A_A") (pintype "passive"))
      (node (ref "DS402") (pin "A") (pinfunction "A_A") (pintype "passive"))
      (node (ref "J202") (pin "1") (pinfunction "1_1") (pintype "passive"))
      (node (ref "J202") (pin "4") (pinfunction "4_4") (pintype "passive"))
      (node (ref "J203") (pin "2") (pinfunction "2_2") (pintype "passive"))
      (node (ref "R101") (pin "2") (pinfunction "2_2") (pintype "passive"))
      (node (ref "R104") (pin "1") (pinfunction "1_1") (pintype "passive"))
      (node (ref "U101") (pin "18") (pinfunction "AVCC_18") (pintype "bidirectional"))
      (node (ref "U101") (pin "4") (pinfunction "VCC_4") (pintype "bidirectional"))
      (node (ref "U101") (pin "6") (pinfunction "VCC_6") (pintype "bidirectional"))
    )
    (net (code "54") (name "PP5V0_USB") (class "Default")
      (node (ref "J202") (pin "14") (pinfunction "14_14") (pintype "passive"))
      (node (ref "J401") (pin "VBUS1") (pinfunction "VBUS_VBUS1") (pintype "bidirectional"))
      (node (ref "J402") (pin "3") (pinfunction "3_3") (pintype "passive"))
      (node (ref "R104") (pin "2") (pinfunction "2_2") (pintype "passive"))
      (node (ref "R105") (pin "2") (pinfunction "2_2") (pintype "passive"))
      (node (ref "R301") (pin "2") (pinfunction "2_2") (pintype "passive"))
    )
    (net (code "55") (name "USB_DAT_N") (class "Default")
      (node (ref "J401") (pin "D-1") (pinfunction "D-_D-1") (pintype "bidirectional"))
      (node (ref "R304") (pin "2") (pinfunction "2_2") (pintype "passive"))
    )
    (net (code "56") (name "USB_DAT_P") (class "Default")
      (node (ref "J401") (pin "D+1") (pinfunction "D+_D+1") (pintype "bidirectional"))
      (node (ref "R303") (pin "2") (pinfunction "2_2") (pintype "passive"))
    )
    (net (code "57") (name "USB_ID") (class "Default")
      (node (ref "J401") (pin "ID1") (pinfunction "USBID_ID1") (pintype "bidirectional"))
      (node (ref "R301") (pin "1") (pinfunction "1_1") (pintype "passive"))
      (node (ref "R302") (pin "2") (pinfunction "2_2") (pintype "passive"))
    )
  )
)
